# Sheet1_dsPIC33CDV_OpAmp.net
KiCad netlist of a schematic drawn in Altium Designer
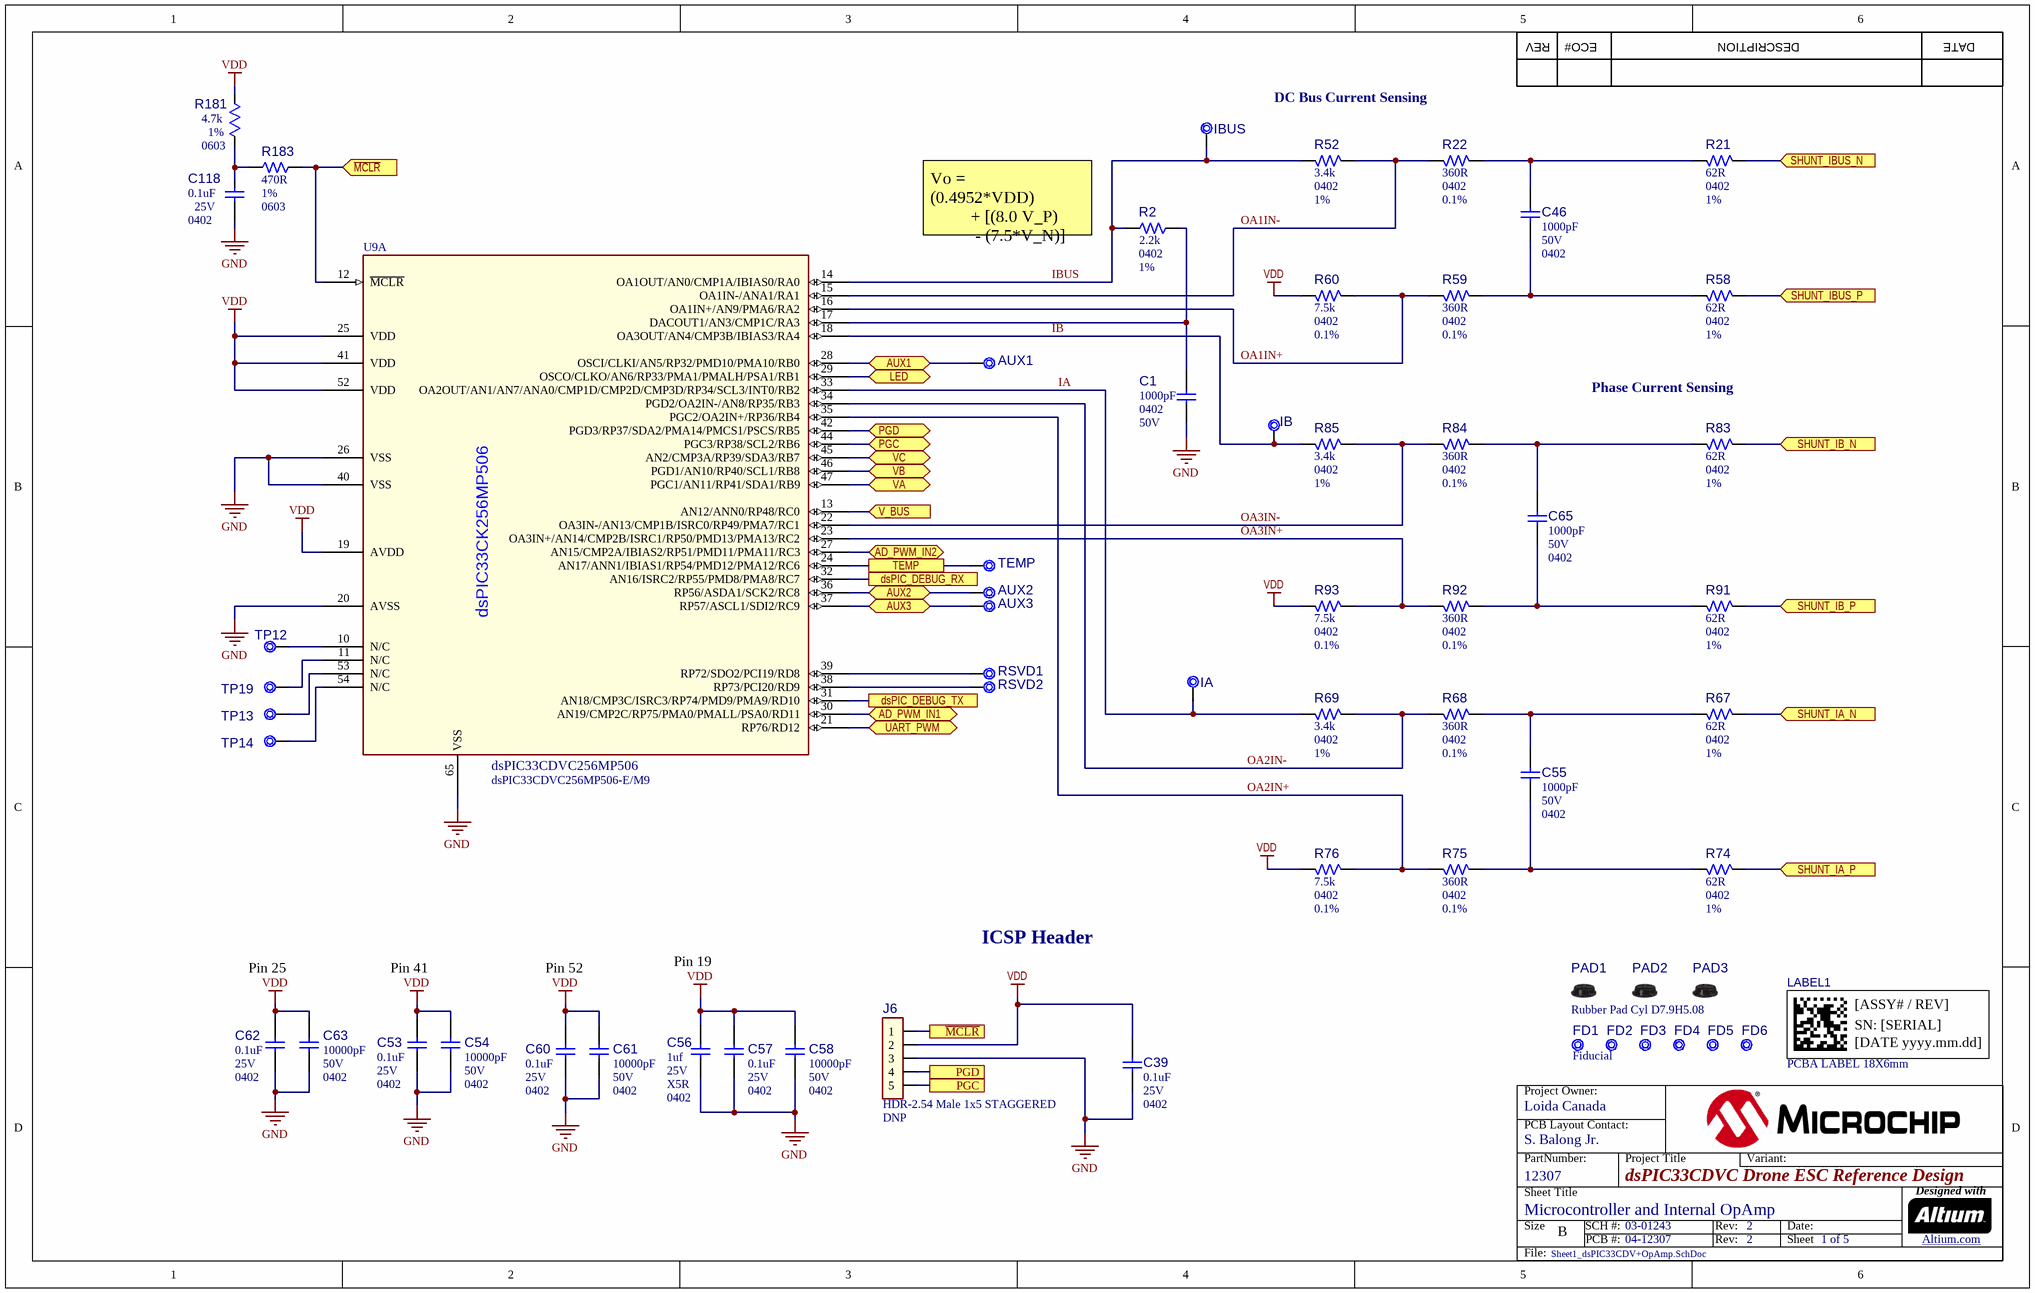
[diagram p0: Sheet1_dsPIC33CDV+OpAmp.SchDoc]

(export (version "E")
  (design (tool "Eeschema 10.0.6"))
  (components
    (comp (ref "AUX1")
      (value "Test Point No BOM")
      (footprint "CON_TP_SMD_D25mil_NoSilk")
      (description "Test Point")
      (fields (field (name "OWNER") "James Boomer"))
      (libsource (lib "MCHP-CDB") (part "Test Point No BOM"))
    )
    (comp (ref "AUX2")
      (value "Test Point No BOM")
      (footprint "TP_TH_0.7PADX0.4HOLE")
      (description "Test Point")
      (fields (field (name "OWNER") "Severino Balong Jr."))
      (libsource (lib "MCHP-CDB") (part "Test Point No BOM"))
    )
    (comp (ref "AUX3")
      (value "Test Point No BOM")
      (footprint "CON_TP_SMD_D25mil_NoSilk")
      (description "Test Point")
      (fields (field (name "OWNER") "James Boomer"))
      (libsource (lib "MCHP-CDB") (part "Test Point No BOM"))
    )
    (comp (ref "C1")
      (value "1000pF")
      (footprint "CAP_C_0402")
      (fields
        (field (name "VOLTAGE") "50V")
        (field (name "PACKAGE") "0402")
        (field (name "TOLERANCE") "5%")
        (field (name "Comment") "Capacitor NP")
        (field (name "OWNER") "Narasimha Murthy")
      )
      (libsource (lib "MCHP-CDB") (part "Capacitor NP"))
    )
    (comp (ref "C39")
      (value "0.1uF")
      (footprint "CAP_C_0402")
      (fields
        (field (name "VOLTAGE") "25V")
        (field (name "PACKAGE") "0402")
        (field (name "TOLERANCE") "10%")
        (field (name "Comment") "Capacitor NP")
        (field (name "OWNER") "Randolph Sobrepena")
      )
      (libsource (lib "MCHP-CDB") (part "Capacitor NP"))
    )
    (comp (ref "C46")
      (value "1000pF")
      (footprint "CAP_C_0402")
      (fields
        (field (name "VOLTAGE") "50V")
        (field (name "PACKAGE") "0402")
        (field (name "TOLERANCE") "5%")
        (field (name "Comment") "Capacitor NP")
        (field (name "OWNER") "Narasimha Murthy")
      )
      (libsource (lib "MCHP-CDB") (part "Capacitor NP"))
    )
    (comp (ref "C53")
      (value "0.1uF")
      (footprint "CAP_C_0402")
      (fields
        (field (name "VOLTAGE") "25V")
        (field (name "PACKAGE") "0402")
        (field (name "TOLERANCE") "10%")
        (field (name "Comment") "Capacitor NP")
        (field (name "OWNER") "Randolph Sobrepena")
      )
      (libsource (lib "MCHP-CDB") (part "Capacitor NP"))
    )
    (comp (ref "C54")
      (value "10000pF")
      (footprint "CAP_C_0402")
      (fields
        (field (name "VOLTAGE") "50V")
        (field (name "PACKAGE") "0402")
        (field (name "TOLERANCE") "10%")
        (field (name "Comment") "Capacitor NP")
        (field (name "OWNER") "Tad Ahlvers")
      )
      (libsource (lib "MCHP-CDB") (part "Capacitor NP"))
    )
    (comp (ref "C55")
      (value "1000pF")
      (footprint "CAP_C_0402")
      (fields
        (field (name "VOLTAGE") "50V")
        (field (name "PACKAGE") "0402")
        (field (name "TOLERANCE") "5%")
        (field (name "Comment") "Capacitor NP")
        (field (name "OWNER") "Narasimha Murthy")
      )
      (libsource (lib "MCHP-CDB") (part "Capacitor NP"))
    )
    (comp (ref "C56")
      (value "1uf")
      (footprint "CAP_C_0402")
      (fields
        (field (name "VOLTAGE") "25V")
        (field (name "PACKAGE") "0402")
        (field (name "TOLERANCE") "10%")
        (field (name "TEMPERATURE COEFFICIENT") "X5R")
        (field (name "Comment") "Capacitor NP")
        (field (name "OWNER") "Tim Moffat")
      )
      (libsource (lib "MCHP-CDB") (part "Capacitor NP"))
    )
    (comp (ref "C57")
      (value "0.1uF")
      (footprint "CAP_C_0402")
      (fields
        (field (name "VOLTAGE") "25V")
        (field (name "PACKAGE") "0402")
        (field (name "TOLERANCE") "10%")
        (field (name "Comment") "Capacitor NP")
        (field (name "OWNER") "Randolph Sobrepena")
      )
      (libsource (lib "MCHP-CDB") (part "Capacitor NP"))
    )
    (comp (ref "C58")
      (value "10000pF")
      (footprint "CAP_C_0402")
      (fields
        (field (name "VOLTAGE") "50V")
        (field (name "PACKAGE") "0402")
        (field (name "TOLERANCE") "10%")
        (field (name "Comment") "Capacitor NP")
        (field (name "OWNER") "Tad Ahlvers")
      )
      (libsource (lib "MCHP-CDB") (part "Capacitor NP"))
    )
    (comp (ref "C60")
      (value "0.1uF")
      (footprint "CAP_C_0402")
      (fields
        (field (name "VOLTAGE") "25V")
        (field (name "PACKAGE") "0402")
        (field (name "TOLERANCE") "10%")
        (field (name "Comment") "Capacitor NP")
        (field (name "OWNER") "Randolph Sobrepena")
      )
      (libsource (lib "MCHP-CDB") (part "Capacitor NP"))
    )
    (comp (ref "C61")
      (value "10000pF")
      (footprint "CAP_C_0402")
      (fields
        (field (name "VOLTAGE") "50V")
        (field (name "PACKAGE") "0402")
        (field (name "TOLERANCE") "10%")
        (field (name "Comment") "Capacitor NP")
        (field (name "OWNER") "Tad Ahlvers")
      )
      (libsource (lib "MCHP-CDB") (part "Capacitor NP"))
    )
    (comp (ref "C62")
      (value "0.1uF")
      (footprint "CAP_C_0402")
      (fields
        (field (name "VOLTAGE") "25V")
        (field (name "PACKAGE") "0402")
        (field (name "TOLERANCE") "10%")
        (field (name "Comment") "Capacitor NP")
        (field (name "OWNER") "Randolph Sobrepena")
      )
      (libsource (lib "MCHP-CDB") (part "Capacitor NP"))
    )
    (comp (ref "C63")
      (value "10000pF")
      (footprint "CAP_C_0402")
      (fields
        (field (name "VOLTAGE") "50V")
        (field (name "PACKAGE") "0402")
        (field (name "TOLERANCE") "10%")
        (field (name "Comment") "Capacitor NP")
        (field (name "OWNER") "Tad Ahlvers")
      )
      (libsource (lib "MCHP-CDB") (part "Capacitor NP"))
    )
    (comp (ref "C65")
      (value "1000pF")
      (footprint "CAP_C_0402")
      (fields
        (field (name "VOLTAGE") "50V")
        (field (name "PACKAGE") "0402")
        (field (name "TOLERANCE") "5%")
        (field (name "Comment") "Capacitor NP")
        (field (name "OWNER") "Narasimha Murthy")
      )
      (libsource (lib "MCHP-CDB") (part "Capacitor NP"))
    )
    (comp (ref "C118")
      (value "0.1uF")
      (footprint "CAP_C_0402")
      (fields
        (field (name "VOLTAGE") "25V")
        (field (name "PACKAGE") "0402")
        (field (name "TOLERANCE") "10%")
        (field (name "Comment") "Capacitor NP")
        (field (name "OWNER") "Randolph Sobrepena")
      )
      (libsource (lib "MCHP-CDB") (part "Capacitor NP"))
    )
    (comp (ref "FD1")
      (value "Fiducial")
      (footprint "Fiducial_1mm")
      (fields (field (name "Comment") "FIDUCIAL ROUND") (field (name "OWNER") "Dragos Danaila"))
      (libsource (lib "MCHP-CDB") (part "FIDUCIAL ROUND"))
    )
    (comp (ref "FD2")
      (value "FIDUCIAL ROUND")
      (footprint "Fiducial_1mm")
      (description "Fiducial")
      (fields (field (name "OWNER") "Dragos Danaila"))
      (libsource (lib "MCHP-CDB") (part "FIDUCIAL ROUND"))
    )
    (comp (ref "FD3")
      (value "FIDUCIAL ROUND")
      (footprint "Fiducial_1mm")
      (description "Fiducial")
      (fields (field (name "OWNER") "Dragos Danaila"))
      (libsource (lib "MCHP-CDB") (part "FIDUCIAL ROUND"))
    )
    (comp (ref "FD4")
      (value "FIDUCIAL ROUND")
      (footprint "Fiducial_1mm")
      (description "Fiducial")
      (fields (field (name "OWNER") "Dragos Danaila"))
      (libsource (lib "MCHP-CDB") (part "FIDUCIAL ROUND"))
    )
    (comp (ref "FD5")
      (value "FIDUCIAL ROUND")
      (footprint "Fiducial_1mm")
      (description "Fiducial")
      (fields (field (name "OWNER") "Dragos Danaila"))
      (libsource (lib "MCHP-CDB") (part "FIDUCIAL ROUND"))
    )
    (comp (ref "FD6")
      (value "FIDUCIAL ROUND")
      (footprint "Fiducial_1mm")
      (description "Fiducial")
      (fields (field (name "OWNER") "Dragos Danaila"))
      (libsource (lib "MCHP-CDB") (part "FIDUCIAL ROUND"))
    )
    (comp (ref "IA")
      (value "Test Point No BOM")
      (footprint "CON_TP_SMD_D25mil_NoSilk")
      (description "Test Point")
      (fields (field (name "OWNER") "James Boomer"))
      (libsource (lib "MCHP-CDB") (part "Test Point No BOM"))
    )
    (comp (ref "IB")
      (value "Test Point No BOM")
      (footprint "CON_TP_SMD_D25mil_NoSilk")
      (description "Test Point")
      (fields (field (name "OWNER") "James Boomer"))
      (libsource (lib "MCHP-CDB") (part "Test Point No BOM"))
    )
    (comp (ref "IBUS")
      (value "Test Point No BOM")
      (footprint "TP_TH_0.7PADX0.4HOLE")
      (description "Test Point")
      (fields (field (name "OWNER") "Severino Balong Jr."))
      (libsource (lib "") (part "Test Point No BOM_1"))
    )
    (comp (ref "J6")
      (value "HDR-2.54 Male 1x5 STAGGERED")
      (footprint "HDR_M_2.54_1x5_STAGGERED")
      (fields (field (name "POPULATED") "DNP") (field (name "OWNER") "Severino Balong Jr."))
      (libsource (lib "MCHP-CDB") (part "Header 1x5"))
    )
    (comp (ref "LABEL1")
      (value "PCBA LABEL 18X6mm")
      (footprint "08-10015")
      (fields (field (name "Comment") "08-10015") (field (name "OWNER") "Mark Loper"))
      (libsource (lib "MCHP-CDB") (part "08-10015"))
    )
    (comp (ref "PAD1")
      (value "Rubber Pad Cyl D7.9H5.08")
      (footprint "BUMP_3M_SJ61A1_CYLINDRICAL_BLACK_D7.9H5.08")
      (fields (field (name "Comment") "Rubber Pad Cylindrical") (field (name "OWNER") "Bogdan Popescu"))
      (libsource (lib "MCHP-CDB") (part "Rubber Pad Cylindrical"))
    )
    (comp (ref "PAD2")
      (value "Rubber Pad Cylindrical")
      (footprint "BUMP_3M_SJ61A1_CYLINDRICAL_BLACK_D7.9H5.08")
      (fields (field (name "OWNER") "Bogdan Popescu"))
      (libsource (lib "MCHP-CDB") (part "Rubber Pad Cylindrical"))
    )
    (comp (ref "PAD3")
      (value "Rubber Pad Cylindrical")
      (footprint "BUMP_3M_SJ61A1_CYLINDRICAL_BLACK_D7.9H5.08")
      (fields (field (name "OWNER") "Bogdan Popescu"))
      (libsource (lib "MCHP-CDB") (part "Rubber Pad Cylindrical"))
    )
    (comp (ref "R2")
      (value "2.2k")
      (footprint "RES_C_0402")
      (description "Resistor")
      (fields
        (field (name "PACKAGE") "0402")
        (field (name "TOLERANCE") "1%")
        (field (name "VOLTAGE") "50V")
        (field (name "POWER") "1/10W")
        (field (name "OWNER") "Tad Ahlvers")
      )
      (libsource (lib "MCHP-CDB") (part "Resistor"))
    )
    (comp (ref "R21")
      (value "62R")
      (footprint "RES_C_0402")
      (description "Resistor")
      (fields
        (field (name "PACKAGE") "0402")
        (field (name "TOLERANCE") "1%")
        (field (name "VOLTAGE") "50V")
        (field (name "POWER") "1/16W")
        (field (name "OWNER") "Dragos Danaila")
      )
      (libsource (lib "MCHP-CDB") (part "Resistor"))
    )
    (comp (ref "R22")
      (value "360R")
      (footprint "RES_C_0402")
      (description "Resistor")
      (fields
        (field (name "PACKAGE") "0402")
        (field (name "TOLERANCE") "0.1%")
        (field (name "POWER") "1/10W")
        (field (name "VOLTAGE") "50V")
        (field (name "OWNER") "Cristian Papuc")
      )
      (libsource (lib "MCHP-CDB") (part "Resistor"))
    )
    (comp (ref "R52")
      (value "3.4k")
      (footprint "RES_C_0402")
      (description "Resistor")
      (fields
        (field (name "PACKAGE") "0402")
        (field (name "TOLERANCE") "1%")
        (field (name "POWER") "1/10W")
        (field (name "VOLTAGE") "50V")
        (field (name "OWNER") "Deepak Kariyappa")
      )
      (libsource (lib "MCHP-CDB") (part "Resistor"))
    )
    (comp (ref "R58")
      (value "62R")
      (footprint "RES_C_0402")
      (description "Resistor")
      (fields
        (field (name "PACKAGE") "0402")
        (field (name "TOLERANCE") "1%")
        (field (name "VOLTAGE") "50V")
        (field (name "POWER") "1/16W")
        (field (name "OWNER") "Dragos Danaila")
      )
      (libsource (lib "MCHP-CDB") (part "Resistor"))
    )
    (comp (ref "R59")
      (value "360R")
      (footprint "RES_C_0402")
      (description "Resistor")
      (fields
        (field (name "PACKAGE") "0402")
        (field (name "TOLERANCE") "0.1%")
        (field (name "POWER") "1/10W")
        (field (name "VOLTAGE") "50V")
        (field (name "OWNER") "Cristian Papuc")
      )
      (libsource (lib "MCHP-CDB") (part "Resistor"))
    )
    (comp (ref "R60")
      (value "7.5k")
      (footprint "RES_C_0402")
      (description "Resistor")
      (fields
        (field (name "PACKAGE") "0402")
        (field (name "TOLERANCE") "0.1%")
        (field (name "POWER") "1/16W")
        (field (name "OWNER") "Narasimha Murthy")
      )
      (libsource (lib "MCHP-CDB") (part "Resistor"))
    )
    (comp (ref "R67")
      (value "62R")
      (footprint "RES_C_0402")
      (description "Resistor")
      (fields
        (field (name "PACKAGE") "0402")
        (field (name "TOLERANCE") "1%")
        (field (name "VOLTAGE") "50V")
        (field (name "POWER") "1/16W")
        (field (name "OWNER") "Dragos Danaila")
      )
      (libsource (lib "MCHP-CDB") (part "Resistor"))
    )
    (comp (ref "R68")
      (value "360R")
      (footprint "RES_C_0402")
      (description "Resistor")
      (fields
        (field (name "PACKAGE") "0402")
        (field (name "TOLERANCE") "0.1%")
        (field (name "POWER") "1/10W")
        (field (name "VOLTAGE") "50V")
        (field (name "OWNER") "Cristian Papuc")
      )
      (libsource (lib "MCHP-CDB") (part "Resistor"))
    )
    (comp (ref "R69")
      (value "3.4k")
      (footprint "RES_C_0402")
      (description "Resistor")
      (fields
        (field (name "PACKAGE") "0402")
        (field (name "TOLERANCE") "1%")
        (field (name "POWER") "1/10W")
        (field (name "VOLTAGE") "50V")
        (field (name "OWNER") "Deepak Kariyappa")
      )
      (libsource (lib "MCHP-CDB") (part "Resistor"))
    )
    (comp (ref "R74")
      (value "62R")
      (footprint "RES_C_0402")
      (description "Resistor")
      (fields
        (field (name "PACKAGE") "0402")
        (field (name "TOLERANCE") "1%")
        (field (name "VOLTAGE") "50V")
        (field (name "POWER") "1/16W")
        (field (name "OWNER") "Dragos Danaila")
      )
      (libsource (lib "MCHP-CDB") (part "Resistor"))
    )
    (comp (ref "R75")
      (value "360R")
      (footprint "RES_C_0402")
      (description "Resistor")
      (fields
        (field (name "PACKAGE") "0402")
        (field (name "TOLERANCE") "0.1%")
        (field (name "POWER") "1/10W")
        (field (name "VOLTAGE") "50V")
        (field (name "OWNER") "Cristian Papuc")
      )
      (libsource (lib "MCHP-CDB") (part "Resistor"))
    )
    (comp (ref "R76")
      (value "7.5k")
      (footprint "RES_C_0402")
      (description "Resistor")
      (fields
        (field (name "PACKAGE") "0402")
        (field (name "TOLERANCE") "0.1%")
        (field (name "POWER") "1/16W")
        (field (name "OWNER") "Narasimha Murthy")
      )
      (libsource (lib "MCHP-CDB") (part "Resistor"))
    )
    (comp (ref "R83")
      (value "62R")
      (footprint "RES_C_0402")
      (description "Resistor")
      (fields
        (field (name "PACKAGE") "0402")
        (field (name "TOLERANCE") "1%")
        (field (name "VOLTAGE") "50V")
        (field (name "POWER") "1/16W")
        (field (name "OWNER") "Dragos Danaila")
      )
      (libsource (lib "MCHP-CDB") (part "Resistor"))
    )
    (comp (ref "R84")
      (value "360R")
      (footprint "RES_C_0402")
      (description "Resistor")
      (fields
        (field (name "PACKAGE") "0402")
        (field (name "TOLERANCE") "0.1%")
        (field (name "POWER") "1/10W")
        (field (name "VOLTAGE") "50V")
        (field (name "OWNER") "Cristian Papuc")
      )
      (libsource (lib "MCHP-CDB") (part "Resistor"))
    )
    (comp (ref "R85")
      (value "3.4k")
      (footprint "RES_C_0402")
      (description "Resistor")
      (fields
        (field (name "PACKAGE") "0402")
        (field (name "TOLERANCE") "1%")
        (field (name "POWER") "1/10W")
        (field (name "VOLTAGE") "50V")
        (field (name "OWNER") "Deepak Kariyappa")
      )
      (libsource (lib "MCHP-CDB") (part "Resistor"))
    )
    (comp (ref "R91")
      (value "62R")
      (footprint "RES_C_0402")
      (description "Resistor")
      (fields
        (field (name "PACKAGE") "0402")
        (field (name "TOLERANCE") "1%")
        (field (name "VOLTAGE") "50V")
        (field (name "POWER") "1/16W")
        (field (name "OWNER") "Dragos Danaila")
      )
      (libsource (lib "MCHP-CDB") (part "Resistor"))
    )
    (comp (ref "R92")
      (value "360R")
      (footprint "RES_C_0402")
      (description "Resistor")
      (fields
        (field (name "PACKAGE") "0402")
        (field (name "TOLERANCE") "0.1%")
        (field (name "POWER") "1/10W")
        (field (name "VOLTAGE") "50V")
        (field (name "OWNER") "Cristian Papuc")
      )
      (libsource (lib "MCHP-CDB") (part "Resistor"))
    )
    (comp (ref "R93")
      (value "7.5k")
      (footprint "RES_C_0402")
      (description "Resistor")
      (fields
        (field (name "PACKAGE") "0402")
        (field (name "TOLERANCE") "0.1%")
        (field (name "POWER") "1/16W")
        (field (name "OWNER") "Narasimha Murthy")
      )
      (libsource (lib "MCHP-CDB") (part "Resistor"))
    )
    (comp (ref "R181")
      (value "4.7k")
      (footprint "RES_C_0603")
      (description "Resistor")
      (fields
        (field (name "TOLERANCE") "1%")
        (field (name "PACKAGE") "0603")
        (field (name "POWER") "1/10W")
        (field (name "VOLTAGE") "75V")
      )
      (libsource (lib "") (part "Resistor_1"))
    )
    (comp (ref "R183")
      (value "470R")
      (footprint "RES_C_0603")
      (description "Resistor")
      (fields
        (field (name "TOLERANCE") "1%")
        (field (name "PACKAGE") "0603")
        (field (name "POWER") "1/10W")
        (field (name "VOLTAGE") "50V")
      )
      (libsource (lib "") (part "Resistor_2"))
    )
    (comp (ref "RSVD1")
      (value "Test Point No BOM")
      (footprint "CON_TP_SMD_D25mil_NoSilk")
      (description "Test Point")
      (fields (field (name "OWNER") "James Boomer"))
      (libsource (lib "MCHP-CDB") (part "Test Point No BOM"))
    )
    (comp (ref "RSVD2")
      (value "Test Point No BOM")
      (footprint "CON_TP_SMD_D25mil_NoSilk")
      (description "Test Point")
      (fields (field (name "OWNER") "James Boomer"))
      (libsource (lib "MCHP-CDB") (part "Test Point No BOM"))
    )
    (comp (ref "TEMP")
      (value "Test Point No BOM")
      (footprint "TP_TH_0.7PADX0.4HOLE")
      (description "Test Point")
      (fields (field (name "OWNER") "Severino Balong Jr."))
      (libsource (lib "MCHP-CDB") (part "Test Point No BOM"))
    )
    (comp (ref "TP12")
      (value "Test Point No BOM")
      (footprint "CON_TP_SMD_D25mil_NoSilk")
      (description "Test Point")
      (fields (field (name "OWNER") "James Boomer"))
      (libsource (lib "MCHP-CDB") (part "Test Point No BOM"))
    )
    (comp (ref "TP13")
      (value "Test Point No BOM")
      (footprint "CON_TP_SMD_D25mil_NoSilk")
      (description "Test Point")
      (fields (field (name "OWNER") "James Boomer"))
      (libsource (lib "MCHP-CDB") (part "Test Point No BOM"))
    )
    (comp (ref "TP14")
      (value "Test Point No BOM")
      (footprint "CON_TP_SMD_D25mil_NoSilk")
      (description "Test Point")
      (fields (field (name "OWNER") "James Boomer"))
      (libsource (lib "MCHP-CDB") (part "Test Point No BOM"))
    )
    (comp (ref "TP19")
      (value "Test Point No BOM")
      (footprint "CON_TP_SMD_D25mil_NoSilk")
      (description "Test Point")
      (fields (field (name "OWNER") "James Boomer"))
      (libsource (lib "MCHP-CDB") (part "Test Point No BOM"))
    )
    (comp (ref "U9")
      (value "dsPIC33CDVC256MP506-E/M9")
      (footprint "QFN-64_9X9_3EP_M9")
      (fields
        (field (name "Comment") "dsPIC33CDVC256MP506_VGQFN-64")
        (field (name "OWNER") "Narasimha Murthy")
      )
      (libsource (lib "MCHP-CDB") (part "dsPIC33CDVC256MP506_VGQFN-64"))
    )
  )
  (nets
    (net (code "1") (name "/AD_PWM_IN1") (class "Default")
      (node (ref "U9") (pin "30") (pinfunction "AN19/CMP2C/RP75/PMA0/PMALL/PSA0/RD11_30") (pintype "bidirectional"))
    )
    (net (code "2") (name "/AD_PWM_IN2") (class "Default")
      (node (ref "U9") (pin "27") (pinfunction "AN15/CMP2A/IBIAS2/RP51/PMD11/PMA11/RC3_27") (pintype "bidirectional"))
    )
    (net (code "3") (name "/AUX1") (class "Default")
      (node (ref "AUX1") (pin "1") (pinfunction "1_1") (pintype "passive"))
      (node (ref "U9") (pin "28") (pinfunction "OSCI/CLKI/AN5/RP32/PMD10/PMA10/RB0_28") (pintype "bidirectional"))
    )
    (net (code "4") (name "/AUX2") (class "Default")
      (node (ref "AUX2") (pin "1") (pinfunction "1_1") (pintype "passive"))
      (node (ref "U9") (pin "36") (pinfunction "RP56/ASDA1/SCK2/RC8_36") (pintype "bidirectional"))
    )
    (net (code "5") (name "/AUX3") (class "Default")
      (node (ref "AUX3") (pin "1") (pinfunction "1_1") (pintype "passive"))
      (node (ref "U9") (pin "37") (pinfunction "RP57/ASCL1/SDI2/RC9_37") (pintype "bidirectional"))
    )
    (net (code "6") (name "/IA") (class "Default")
      (node (ref "IA") (pin "1") (pinfunction "1_1") (pintype "passive"))
      (node (ref "R69") (pin "2") (pinfunction "2_2") (pintype "passive"))
      (node (ref "U9") (pin "33") (pinfunction "OA2OUT/AN1/AN7/ANA0/CMP1D/CMP2D/CMP3D/RP34/SCL3/INT0/RB2_33") (pintype "bidirectional"))
    )
    (net (code "7") (name "/IB") (class "Default")
      (node (ref "IB") (pin "1") (pinfunction "1_1") (pintype "passive"))
      (node (ref "R85") (pin "2") (pinfunction "2_2") (pintype "passive"))
      (node (ref "U9") (pin "18") (pinfunction "OA3OUT/AN4/CMP3B/IBIAS3/RA4_18") (pintype "bidirectional"))
    )
    (net (code "8") (name "/IBUS") (class "Default")
      (node (ref "IBUS") (pin "1") (pinfunction "1_1") (pintype "passive"))
      (node (ref "R2") (pin "1") (pinfunction "1_1") (pintype "passive"))
      (node (ref "R52") (pin "2") (pinfunction "2_2") (pintype "passive"))
      (node (ref "U9") (pin "14") (pinfunction "OA1OUT/AN0/CMP1A/IBIAS0/RA0_14") (pintype "bidirectional"))
    )
    (net (code "9") (name "/LED") (class "Default")
      (node (ref "U9") (pin "29") (pinfunction "OSCO/CLKO/AN6/RP33/PMA1/PMALH/PSA1/RB1_29") (pintype "bidirectional"))
    )
    (net (code "10") (name "/OA1IN+") (class "Default")
      (node (ref "R59") (pin "2") (pinfunction "2_2") (pintype "passive"))
      (node (ref "R60") (pin "1") (pinfunction "1_1") (pintype "passive"))
      (node (ref "U9") (pin "16") (pinfunction "OA1IN+/AN9/PMA6/RA2_16") (pintype "bidirectional"))
    )
    (net (code "11") (name "/OA1IN-") (class "Default")
      (node (ref "R22") (pin "2") (pinfunction "2_2") (pintype "passive"))
      (node (ref "R52") (pin "1") (pinfunction "1_1") (pintype "passive"))
      (node (ref "U9") (pin "15") (pinfunction "OA1IN-/ANA1/RA1_15") (pintype "bidirectional"))
    )
    (net (code "12") (name "/OA2IN+") (class "Default")
      (node (ref "R75") (pin "2") (pinfunction "2_2") (pintype "passive"))
      (node (ref "R76") (pin "1") (pinfunction "1_1") (pintype "passive"))
      (node (ref "U9") (pin "35") (pinfunction "PGC2/OA2IN+/RP36/RB4_35") (pintype "bidirectional"))
    )
    (net (code "13") (name "/OA2IN-") (class "Default")
      (node (ref "R68") (pin "2") (pinfunction "2_2") (pintype "passive"))
      (node (ref "R69") (pin "1") (pinfunction "1_1") (pintype "passive"))
      (node (ref "U9") (pin "34") (pinfunction "PGD2/OA2IN-/AN8/RP35/RB3_34") (pintype "bidirectional"))
    )
    (net (code "14") (name "/OA3IN+") (class "Default")
      (node (ref "R92") (pin "2") (pinfunction "2_2") (pintype "passive"))
      (node (ref "R93") (pin "1") (pinfunction "1_1") (pintype "passive"))
      (node (ref "U9") (pin "23") (pinfunction "OA3IN+/AN14/CMP2B/ISRC1/RP50/PMD13/PMA13/RC2_23") (pintype "bidirectional"))
    )
    (net (code "15") (name "/OA3IN-") (class "Default")
      (node (ref "R84") (pin "2") (pinfunction "2_2") (pintype "passive"))
      (node (ref "R85") (pin "1") (pinfunction "1_1") (pintype "passive"))
      (node (ref "U9") (pin "22") (pinfunction "OA3IN-/AN13/CMP1B/ISRC0/RP49/PMA7/RC1_22") (pintype "bidirectional"))
    )
    (net (code "16") (name "/PGC") (class "Default")
      (node (ref "J6") (pin "5") (pinfunction "5_5") (pintype "passive"))
      (node (ref "U9") (pin "44") (pinfunction "PGC3/RP38/SCL2/RB6_44") (pintype "bidirectional"))
    )
    (net (code "17") (name "/PGD") (class "Default")
      (node (ref "J6") (pin "4") (pinfunction "4_4") (pintype "passive"))
      (node (ref "U9") (pin "42") (pinfunction "PGD3/RP37/SDA2/PMA14/PMCS1/PSCS/RB5_42") (pintype "bidirectional"))
    )
    (net (code "18") (name "/SHUNT_IA_N") (class "Default")
      (node (ref "R67") (pin "1") (pinfunction "1_1") (pintype "passive"))
    )
    (net (code "19") (name "/SHUNT_IA_P") (class "Default")
      (node (ref "R74") (pin "1") (pinfunction "1_1") (pintype "passive"))
    )
    (net (code "20") (name "/SHUNT_IBUS_N") (class "Default")
      (node (ref "R21") (pin "1") (pinfunction "1_1") (pintype "passive"))
    )
    (net (code "21") (name "/SHUNT_IBUS_P") (class "Default")
      (node (ref "R58") (pin "1") (pinfunction "1_1") (pintype "passive"))
    )
    (net (code "22") (name "/SHUNT_IB_N") (class "Default")
      (node (ref "R83") (pin "1") (pinfunction "1_1") (pintype "passive"))
    )
    (net (code "23") (name "/SHUNT_IB_P") (class "Default")
      (node (ref "R91") (pin "1") (pinfunction "1_1") (pintype "passive"))
    )
    (net (code "24") (name "/TEMP") (class "Default")
      (node (ref "TEMP") (pin "1") (pinfunction "1_1") (pintype "passive"))
      (node (ref "U9") (pin "24") (pinfunction "AN17/ANN1/IBIAS1/RP54/PMD12/PMA12/RC6_24") (pintype "bidirectional"))
    )
    (net (code "25") (name "/UART_PWM") (class "Default")
      (node (ref "U9") (pin "21") (pinfunction "RP76/RD12_21") (pintype "bidirectional"))
    )
    (net (code "26") (name "/VA") (class "Default")
      (node (ref "U9") (pin "47") (pinfunction "PGC1/AN11/RP41/SDA1/RB9_47") (pintype "bidirectional"))
    )
    (net (code "27") (name "/VB") (class "Default")
      (node (ref "U9") (pin "46") (pinfunction "PGD1/AN10/RP40/SCL1/RB8_46") (pintype "bidirectional"))
    )
    (net (code "28") (name "/VC") (class "Default")
      (node (ref "U9") (pin "45") (pinfunction "AN2/CMP3A/RP39/SDA3/RB7_45") (pintype "bidirectional"))
    )
    (net (code "29") (name "/V_BUS") (class "Default")
      (node (ref "U9") (pin "13") (pinfunction "AN12/ANN0/RP48/RC0_13") (pintype "bidirectional"))
    )
    (net (code "30") (name "/dsPIC_DEBUG_RX") (class "Default")
      (node (ref "U9") (pin "32") (pinfunction "AN16/ISRC2/RP55/PMD8/PMA8/RC7_32") (pintype "bidirectional"))
    )
    (net (code "31") (name "/dsPIC_DEBUG_TX") (class "Default")
      (node (ref "U9") (pin "31") (pinfunction "AN18/CMP3C/ISRC3/RP74/PMD9/PMA9/RD10_31") (pintype "bidirectional"))
    )
    (net (code "32") (name "/~{MCLR}") (class "Default")
      (node (ref "J6") (pin "1") (pinfunction "1_1") (pintype "passive"))
      (node (ref "R183") (pin "2") (pinfunction "2_2") (pintype "passive"))
      (node (ref "U9") (pin "12") (pinfunction "~{MCLR}_12") (pintype "input"))
    )
    (net (code "33") (name "GND") (class "Default")
      (node (ref "C1") (pin "2") (pinfunction "2_2") (pintype "passive"))
      (node (ref "C118") (pin "1") (pinfunction "1_1") (pintype "passive"))
      (node (ref "C39") (pin "1") (pinfunction "1_1") (pintype "passive"))
      (node (ref "C53") (pin "1") (pinfunction "1_1") (pintype "passive"))
      (node (ref "C54") (pin "1") (pinfunction "1_1") (pintype "passive"))
      (node (ref "C56") (pin "1") (pinfunction "1_1") (pintype "passive"))
      (node (ref "C57") (pin "1") (pinfunction "1_1") (pintype "passive"))
      (node (ref "C58") (pin "1") (pinfunction "1_1") (pintype "passive"))
      (node (ref "C60") (pin "1") (pinfunction "1_1") (pintype "passive"))
      (node (ref "C61") (pin "1") (pinfunction "1_1") (pintype "passive"))
      (node (ref "C62") (pin "1") (pinfunction "1_1") (pintype "passive"))
      (node (ref "C63") (pin "1") (pinfunction "1_1") (pintype "passive"))
      (node (ref "J6") (pin "3") (pinfunction "3_3") (pintype "passive"))
      (node (ref "U9") (pin "20") (pinfunction "AVSS_20") (pintype "power_in"))
      (node (ref "U9") (pin "26") (pinfunction "VSS_26") (pintype "power_in"))
      (node (ref "U9") (pin "40") (pinfunction "VSS_40") (pintype "power_in"))
      (node (ref "U9") (pin "65") (pinfunction "VSS_65") (pintype "power_in"))
    )
    (net (code "34") (name "Net-(C46-Pad1)") (class "Default")
      (node (ref "C46") (pin "1") (pinfunction "1_1") (pintype "passive"))
      (node (ref "R58") (pin "2") (pinfunction "2_2") (pintype "passive"))
      (node (ref "R59") (pin "1") (pinfunction "1_1") (pintype "passive"))
    )
    (net (code "35") (name "Net-(C46-Pad2)") (class "Default")
      (node (ref "C46") (pin "2") (pinfunction "2_2") (pintype "passive"))
      (node (ref "R21") (pin "2") (pinfunction "2_2") (pintype "passive"))
      (node (ref "R22") (pin "1") (pinfunction "1_1") (pintype "passive"))
    )
    (net (code "36") (name "Net-(C55-Pad1)") (class "Default")
      (node (ref "C55") (pin "1") (pinfunction "1_1") (pintype "passive"))
      (node (ref "R74") (pin "2") (pinfunction "2_2") (pintype "passive"))
      (node (ref "R75") (pin "1") (pinfunction "1_1") (pintype "passive"))
    )
    (net (code "37") (name "Net-(C55-Pad2)") (class "Default")
      (node (ref "C55") (pin "2") (pinfunction "2_2") (pintype "passive"))
      (node (ref "R67") (pin "2") (pinfunction "2_2") (pintype "passive"))
      (node (ref "R68") (pin "1") (pinfunction "1_1") (pintype "passive"))
    )
    (net (code "38") (name "Net-(C65-Pad1)") (class "Default")
      (node (ref "C65") (pin "1") (pinfunction "1_1") (pintype "passive"))
      (node (ref "R91") (pin "2") (pinfunction "2_2") (pintype "passive"))
      (node (ref "R92") (pin "1") (pinfunction "1_1") (pintype "passive"))
    )
    (net (code "39") (name "Net-(C65-Pad2)") (class "Default")
      (node (ref "C65") (pin "2") (pinfunction "2_2") (pintype "passive"))
      (node (ref "R83") (pin "2") (pinfunction "2_2") (pintype "passive"))
      (node (ref "R84") (pin "1") (pinfunction "1_1") (pintype "passive"))
    )
    (net (code "40") (name "Net-(C118-Pad2)") (class "Default")
      (node (ref "C118") (pin "2") (pinfunction "2_2") (pintype "passive"))
      (node (ref "R181") (pin "2") (pinfunction "2_2") (pintype "passive"))
      (node (ref "R183") (pin "1") (pinfunction "1_1") (pintype "passive"))
    )
    (net (code "41") (name "Net-(TP12-Pad1)") (class "Default")
      (node (ref "TP12") (pin "1") (pinfunction "1_1") (pintype "passive"))
      (node (ref "U9") (pin "10") (pinfunction "N/C_10") (pintype "passive"))
    )
    (net (code "42") (name "Net-(TP13-Pad1)") (class "Default")
      (node (ref "TP13") (pin "1") (pinfunction "1_1") (pintype "passive"))
      (node (ref "U9") (pin "53") (pinfunction "N/C_53") (pintype "passive"))
    )
    (net (code "43") (name "Net-(TP14-Pad1)") (class "Default")
      (node (ref "TP14") (pin "1") (pinfunction "1_1") (pintype "passive"))
      (node (ref "U9") (pin "54") (pinfunction "N/C_54") (pintype "passive"))
    )
    (net (code "44") (name "Net-(TP19-Pad1)") (class "Default")
      (node (ref "TP19") (pin "1") (pinfunction "1_1") (pintype "passive"))
      (node (ref "U9") (pin "11") (pinfunction "N/C_11") (pintype "passive"))
    )
    (net (code "45") (name "Net-(U9A-DACOUT1{slash}AN3{slash}CMP1C{slash}RA3)") (class "Default")
      (node (ref "C1") (pin "1") (pinfunction "1_1") (pintype "passive"))
      (node (ref "R2") (pin "2") (pinfunction "2_2") (pintype "passive"))
      (node (ref "U9") (pin "17") (pinfunction "DACOUT1/AN3/CMP1C/RA3_17") (pintype "bidirectional"))
    )
    (net (code "46") (name "Net-(U9A-RP72{slash}SDO2{slash}PCI19{slash}RD8)") (class "Default")
      (node (ref "RSVD1") (pin "1") (pinfunction "1_1") (pintype "passive"))
      (node (ref "U9") (pin "39") (pinfunction "RP72/SDO2/PCI19/RD8_39") (pintype "bidirectional"))
    )
    (net (code "47") (name "Net-(U9A-RP73{slash}PCI20{slash}RD9)") (class "Default")
      (node (ref "RSVD2") (pin "1") (pinfunction "1_1") (pintype "passive"))
      (node (ref "U9") (pin "38") (pinfunction "RP73/PCI20/RD9_38") (pintype "bidirectional"))
    )
    (net (code "48") (name "VDD") (class "Default")
      (node (ref "C39") (pin "2") (pinfunction "2_2") (pintype "passive"))
      (node (ref "C53") (pin "2") (pinfunction "2_2") (pintype "passive"))
      (node (ref "C54") (pin "2") (pinfunction "2_2") (pintype "passive"))
      (node (ref "C56") (pin "2") (pinfunction "2_2") (pintype "passive"))
      (node (ref "C57") (pin "2") (pinfunction "2_2") (pintype "passive"))
      (node (ref "C58") (pin "2") (pinfunction "2_2") (pintype "passive"))
      (node (ref "C60") (pin "2") (pinfunction "2_2") (pintype "passive"))
      (node (ref "C61") (pin "2") (pinfunction "2_2") (pintype "passive"))
      (node (ref "C62") (pin "2") (pinfunction "2_2") (pintype "passive"))
      (node (ref "C63") (pin "2") (pinfunction "2_2") (pintype "passive"))
      (node (ref "J6") (pin "2") (pinfunction "2_2") (pintype "passive"))
      (node (ref "R181") (pin "1") (pinfunction "1_1") (pintype "passive"))
      (node (ref "R60") (pin "2") (pinfunction "2_2") (pintype "passive"))
      (node (ref "R76") (pin "2") (pinfunction "2_2") (pintype "passive"))
      (node (ref "R93") (pin "2") (pinfunction "2_2") (pintype "passive"))
      (node (ref "U9") (pin "19") (pinfunction "AVDD_19") (pintype "power_in"))
      (node (ref "U9") (pin "25") (pinfunction "VDD_25") (pintype "power_in"))
      (node (ref "U9") (pin "41") (pinfunction "VDD_41") (pintype "power_in"))
      (node (ref "U9") (pin "52") (pinfunction "VDD_52") (pintype "power_in"))
    )
    (net (code "49") (name "unconnected-(FD1-Pad1)") (class "Default")
      (node (ref "FD1") (pin "1") (pinfunction "1_1") (pintype "passive"))
    )
    (net (code "50") (name "unconnected-(FD2-Pad1)") (class "Default")
      (node (ref "FD2") (pin "1") (pinfunction "1_1") (pintype "passive"))
    )
    (net (code "51") (name "unconnected-(FD3-Pad1)") (class "Default")
      (node (ref "FD3") (pin "1") (pinfunction "1_1") (pintype "passive"))
    )
    (net (code "52") (name "unconnected-(FD4-Pad1)") (class "Default")
      (node (ref "FD4") (pin "1") (pinfunction "1_1") (pintype "passive"))
    )
    (net (code "53") (name "unconnected-(FD5-Pad1)") (class "Default")
      (node (ref "FD5") (pin "1") (pinfunction "1_1") (pintype "passive"))
    )
    (net (code "54") (name "unconnected-(FD6-Pad1)") (class "Default")
      (node (ref "FD6") (pin "1") (pinfunction "1_1") (pintype "passive"))
    )
  )
)
